# sparkfun-photon-redboard.net
KiCad netlist of a schematic drawn in EAGLE
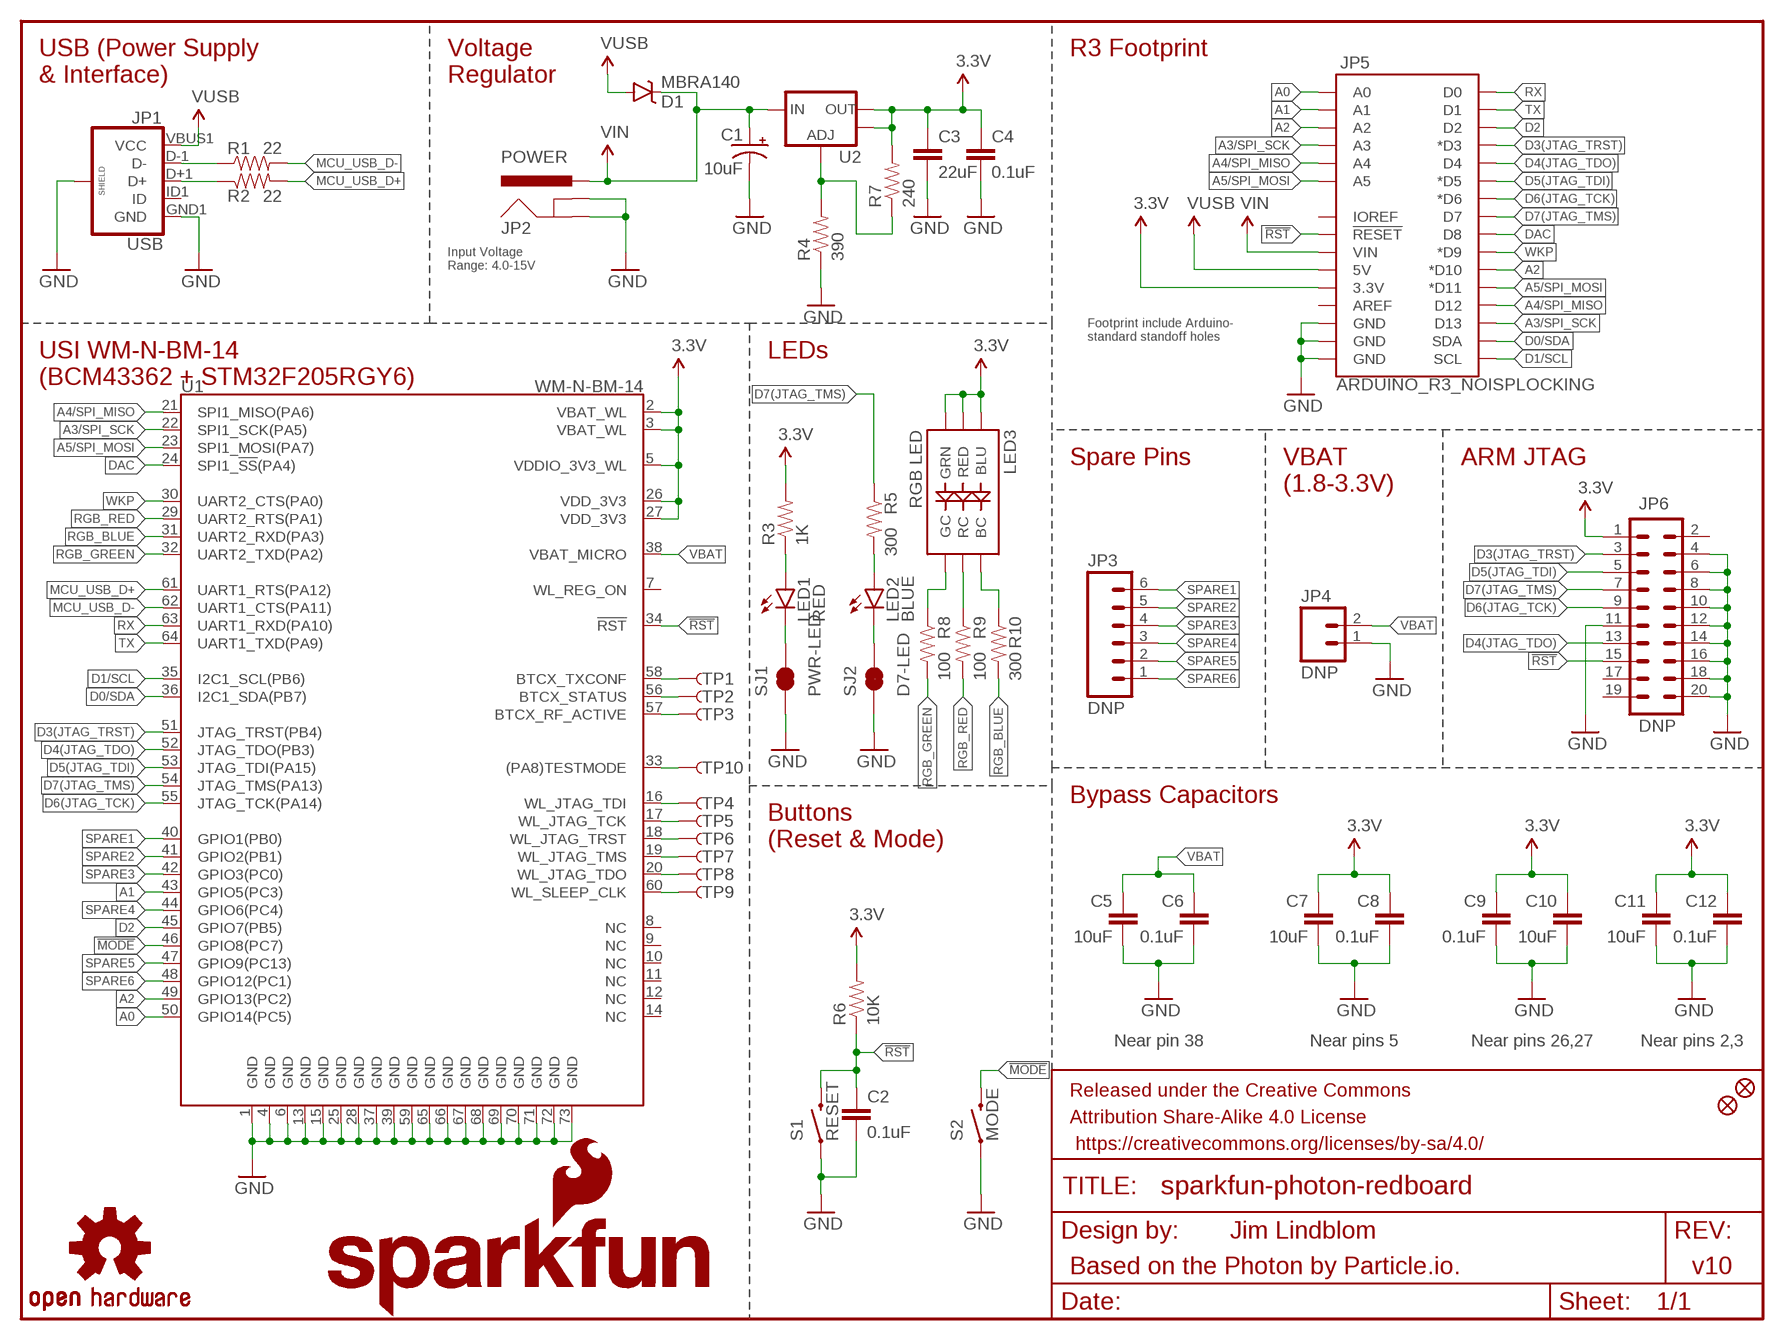
[diagram p0: schematic, sheet 1]

(export (version "E")
  (design (tool "Eeschema 10.0.6"))
  (components
    (comp (ref "C1")
      (value "10uF")
      (footprint "eagle-import:EIA3216")
      (libsource (lib "eagle-import") (part "10UF-16V-10%(TANT)"))
    )
    (comp (ref "C2")
      (value "0.1uF")
      (footprint "eagle-import:0603-CAP")
      (libsource (lib "eagle-import") (part "0.1UF-25V(+80/-20%)(0603)"))
    )
    (comp (ref "C3")
      (value "22uF")
      (footprint "eagle-import:0805")
      (libsource (lib "eagle-import") (part "22UF-6.3V-20%(0805)"))
    )
    (comp (ref "C4")
      (value "0.1uF")
      (footprint "eagle-import:0603-CAP")
      (libsource (lib "eagle-import") (part "0.1UF-25V(+80/-20%)(0603)"))
    )
    (comp (ref "C5")
      (value "10uF")
      (footprint "eagle-import:0603-CAP")
      (libsource (lib "eagle-import") (part "10UF-6.3V-20%(0603)"))
    )
    (comp (ref "C6")
      (value "0.1uF")
      (footprint "eagle-import:0603-CAP")
      (libsource (lib "eagle-import") (part "0.1UF-25V(+80/-20%)(0603)"))
    )
    (comp (ref "C7")
      (value "10uF")
      (footprint "eagle-import:0603-CAP")
      (libsource (lib "eagle-import") (part "10UF-6.3V-20%(0603)"))
    )
    (comp (ref "C8")
      (value "0.1uF")
      (footprint "eagle-import:0603-CAP")
      (libsource (lib "eagle-import") (part "0.1UF-25V(+80/-20%)(0603)"))
    )
    (comp (ref "C9")
      (value "0.1uF")
      (footprint "eagle-import:0603-CAP")
      (libsource (lib "eagle-import") (part "0.1UF-25V(+80/-20%)(0603)"))
    )
    (comp (ref "C10")
      (value "10uF")
      (footprint "eagle-import:0603-CAP")
      (libsource (lib "eagle-import") (part "10UF-6.3V-20%(0603)"))
    )
    (comp (ref "C11")
      (value "10uF")
      (footprint "eagle-import:0603-CAP")
      (libsource (lib "eagle-import") (part "10UF-6.3V-20%(0603)"))
    )
    (comp (ref "C12")
      (value "0.1uF")
      (footprint "eagle-import:0603-CAP")
      (libsource (lib "eagle-import") (part "0.1UF-25V(+80/-20%)(0603)"))
    )
    (comp (ref "D1")
      (value "MBRA140")
      (footprint "eagle-import:SMA-DIODE")
      (libsource (lib "eagle-import") (part "DIODE-SCHOTTKY-MBRA140"))
    )
    (comp (ref "FID1")
      (value "FIDUCIAL1X2")
      (footprint "eagle-import:FIDUCIAL-1X2")
      (libsource (lib "eagle-import") (part "FIDUCIAL1X2"))
    )
    (comp (ref "FID2")
      (value "FIDUCIAL1X2")
      (footprint "eagle-import:FIDUCIAL-1X2")
      (libsource (lib "eagle-import") (part "FIDUCIAL1X2"))
    )
    (comp (ref "FRAME1")
      (value "FRAME-LETTER")
      (footprint "eagle-import:CREATIVE_COMMONS")
      (fields (field (name "DESIGNER") "Jim Lindblom"))
      (libsource (lib "eagle-import") (part "FRAME-LETTER"))
    )
    (comp (ref "JP1")
      (value "USB")
      (footprint "eagle-import:USB-B-MICRO-SMD_V03")
      (libsource (lib "eagle-import") (part "USB_MICROB_PLUGCONN-11752"))
    )
    (comp (ref "JP2")
      (value "POWER")
      (footprint "eagle-import:POWER_JACK_PTH_LOCK")
      (libsource (lib "eagle-import") (part "POWER_JACKPTH_LOCK"))
    )
    (comp (ref "JP3")
      (value "DNP")
      (footprint "eagle-import:1X06")
      (libsource (lib "eagle-import") (part "M06SILK_FEMALE_PTH"))
    )
    (comp (ref "JP4")
      (value "DNP")
      (footprint "eagle-import:1X02")
      (libsource (lib "eagle-import") (part "M02PTH"))
    )
    (comp (ref "JP5")
      (value "ARDUINO_R3_NOISPLOCKING")
      (footprint "eagle-import:ARDUINO_R3_NOISP_LOCKING")
      (libsource (lib "eagle-import") (part "ARDUINO_R3_NOISPLOCKING"))
    )
    (comp (ref "JP6")
      (value "DNP")
      (footprint "eagle-import:2X10")
      (libsource (lib "eagle-import") (part "M10X2"))
    )
    (comp (ref "LED1")
      (value "RED")
      (footprint "eagle-import:LED-1206")
      (libsource (lib "eagle-import") (part "LED-RED1206"))
    )
    (comp (ref "LED2")
      (value "BLUE")
      (footprint "eagle-import:LED-1206")
      (libsource (lib "eagle-import") (part "LED-BLUE1206"))
    )
    (comp (ref "LED3")
      (value "RGB LED")
      (footprint "eagle-import:PLCC-6-LED")
      (libsource (lib "eagle-import") (part "LED-TRICOLOR-NO-COMPLCC-6-SMD"))
    )
    (comp (ref "LOGO1")
      (value "OSHW-LOGOM")
      (footprint "eagle-import:OSHW-LOGO-M")
      (libsource (lib "eagle-import") (part "OSHW-LOGOM"))
    )
    (comp (ref "LOGO2")
      (value "SFE_LOGO_NAME_FLAME.2_INCH")
      (footprint "eagle-import:SFE_LOGO_NAME_FLAME_.2")
      (libsource (lib "eagle-import") (part "SFE_LOGO_NAME_FLAME.2_INCH"))
    )
    (comp (ref "LOGO3")
      (value "SFE_LOGO_NAME_FLAME.4_INCH")
      (footprint "eagle-import:SFE_LOGO_NAME_FLAME_.4")
      (libsource (lib "eagle-import") (part "SFE_LOGO_NAME_FLAME.4_INCH"))
    )
    (comp (ref "R1")
      (value "22")
      (footprint "eagle-import:0603-RES")
      (libsource (lib "eagle-import") (part "22OHM1/10W1%(0603)"))
    )
    (comp (ref "R2")
      (value "22")
      (footprint "eagle-import:0603-RES")
      (libsource (lib "eagle-import") (part "22OHM1/10W1%(0603)"))
    )
    (comp (ref "R3")
      (value "1K")
      (footprint "eagle-import:0603-RES")
      (libsource (lib "eagle-import") (part "1KOHM-1/10W-1%(0603)"))
    )
    (comp (ref "R4")
      (value "390")
      (footprint "eagle-import:0603-RES")
      (libsource (lib "eagle-import") (part "390OHM1/10W1%(0603)"))
    )
    (comp (ref "R5")
      (value "300")
      (footprint "eagle-import:0603-RES")
      (libsource (lib "eagle-import") (part "300OHM-1/10W-1%(0603)"))
    )
    (comp (ref "R6")
      (value "10K")
      (footprint "eagle-import:0603-RES")
      (libsource (lib "eagle-import") (part "10KOHM-1/10W-1%(0603)0603"))
    )
    (comp (ref "R7")
      (value "240")
      (footprint "eagle-import:0603-RES")
      (libsource (lib "eagle-import") (part "240OHM1/10W1%(0603)"))
    )
    (comp (ref "R8")
      (value "100")
      (footprint "eagle-import:0603-RES")
      (libsource (lib "eagle-import") (part "100OHM-1/10W-1%(0603)"))
    )
    (comp (ref "R9")
      (value "100")
      (footprint "eagle-import:0603-RES")
      (libsource (lib "eagle-import") (part "100OHM-1/10W-1%(0603)"))
    )
    (comp (ref "R10")
      (value "300")
      (footprint "eagle-import:0603-RES")
      (libsource (lib "eagle-import") (part "300OHM-1/10W-1%(0603)"))
    )
    (comp (ref "S1")
      (value "RESET")
      (footprint "eagle-import:TACTILE-PTH")
      (libsource (lib "eagle-import") (part "SWITCH-MOMENTARY-2PTH"))
    )
    (comp (ref "S2")
      (value "MODE")
      (footprint "eagle-import:TACTILE-PTH")
      (libsource (lib "eagle-import") (part "SWITCH-MOMENTARY-2PTH"))
    )
    (comp (ref "SJ1")
      (value "PWR-LED")
      (footprint "eagle-import:PAD-JUMPER-2-NC_BY_TRACE_YES_SILK")
      (libsource (lib "eagle-import") (part "JUMPER-PAD-2-NC_BY_TRACE"))
    )
    (comp (ref "SJ2")
      (value "D7-LED")
      (footprint "eagle-import:PAD-JUMPER-2-NC_BY_TRACE_YES_SILK")
      (libsource (lib "eagle-import") (part "JUMPER-PAD-2-NC_BY_TRACE"))
    )
    (comp (ref "TP1")
      (value "TEST-POINTTP_15TH_THRU")
      (footprint "eagle-import:TP_15TH")
      (libsource (lib "eagle-import") (part "TEST-POINTTP_15TH_THRU"))
    )
    (comp (ref "TP2")
      (value "TEST-POINTTP_15TH_THRU")
      (footprint "eagle-import:TP_15TH")
      (libsource (lib "eagle-import") (part "TEST-POINTTP_15TH_THRU"))
    )
    (comp (ref "TP3")
      (value "TEST-POINTTP_15TH_THRU")
      (footprint "eagle-import:TP_15TH")
      (libsource (lib "eagle-import") (part "TEST-POINTTP_15TH_THRU"))
    )
    (comp (ref "TP4")
      (value "TEST-POINTTP_15TH_THRU")
      (footprint "eagle-import:TP_15TH")
      (libsource (lib "eagle-import") (part "TEST-POINTTP_15TH_THRU"))
    )
    (comp (ref "TP5")
      (value "TEST-POINTTP_15TH_THRU")
      (footprint "eagle-import:TP_15TH")
      (libsource (lib "eagle-import") (part "TEST-POINTTP_15TH_THRU"))
    )
    (comp (ref "TP6")
      (value "TEST-POINTTP_15TH_THRU")
      (footprint "eagle-import:TP_15TH")
      (libsource (lib "eagle-import") (part "TEST-POINTTP_15TH_THRU"))
    )
    (comp (ref "TP7")
      (value "TEST-POINTTP_15TH_THRU")
      (footprint "eagle-import:TP_15TH")
      (libsource (lib "eagle-import") (part "TEST-POINTTP_15TH_THRU"))
    )
    (comp (ref "TP8")
      (value "TEST-POINTTP_15TH_THRU")
      (footprint "eagle-import:TP_15TH")
      (libsource (lib "eagle-import") (part "TEST-POINTTP_15TH_THRU"))
    )
    (comp (ref "TP9")
      (value "TEST-POINTTP_15TH_THRU")
      (footprint "eagle-import:TP_15TH")
      (libsource (lib "eagle-import") (part "TEST-POINTTP_15TH_THRU"))
    )
    (comp (ref "TP10")
      (value "TEST-POINTTP_15TH_THRU")
      (footprint "eagle-import:TP_15TH")
      (libsource (lib "eagle-import") (part "TEST-POINTTP_15TH_THRU"))
    )
    (comp (ref "U1")
      (value "WM-N-BM-14")
      (footprint "eagle-import:WM-N-BM-14")
      (libsource (lib "eagle-import") (part "WM-N-BM-14"))
    )
    (comp (ref "U2")
      (value "V_REG_LM1117SOT223")
      (footprint "eagle-import:SOT223")
      (libsource (lib "eagle-import") (part "V_REG_LM1117SOT223"))
    )
  )
  (nets
    (net (code "1") (name "/~{MODE}") (class "Default")
      (node (ref "S2") (pin "3") (pinfunction "2_3") (pintype "passive"))
      (node (ref "U1") (pin "46") (pinfunction "GPIO8(PC7)_46") (pintype "bidirectional"))
    )
    (net (code "2") (name "/~{RST}") (class "Default")
      (node (ref "C2") (pin "1") (pinfunction "1_1") (pintype "passive"))
      (node (ref "JP5") (pin "RESET@1") (pinfunction "~{RESET}_RESET@1") (pintype "bidirectional"))
      (node (ref "JP6") (pin "15") (pinfunction "15_15") (pintype "passive"))
      (node (ref "R6") (pin "1") (pinfunction "1_1") (pintype "passive"))
      (node (ref "S1") (pin "3") (pinfunction "2_3") (pintype "passive"))
      (node (ref "U1") (pin "34") (pinfunction "~{RST}_34") (pintype "bidirectional"))
    )
    (net (code "3") (name "3.3V") (class "Default")
      (node (ref "C10") (pin "1") (pinfunction "1_1") (pintype "passive"))
      (node (ref "C11") (pin "1") (pinfunction "1_1") (pintype "passive"))
      (node (ref "C12") (pin "1") (pinfunction "1_1") (pintype "passive"))
      (node (ref "C3") (pin "1") (pinfunction "1_1") (pintype "passive"))
      (node (ref "C4") (pin "1") (pinfunction "1_1") (pintype "passive"))
      (node (ref "C7") (pin "1") (pinfunction "1_1") (pintype "passive"))
      (node (ref "C8") (pin "1") (pinfunction "1_1") (pintype "passive"))
      (node (ref "C9") (pin "1") (pinfunction "1_1") (pintype "passive"))
      (node (ref "JP5") (pin "3.3V") (pinfunction "3.3V_3.3V") (pintype "bidirectional"))
      (node (ref "JP6") (pin "1") (pinfunction "1_1") (pintype "passive"))
      (node (ref "LED3") (pin "AB") (pinfunction "BLU_AB") (pintype "bidirectional"))
      (node (ref "LED3") (pin "AG") (pinfunction "GRN_AG") (pintype "bidirectional"))
      (node (ref "LED3") (pin "AR") (pinfunction "RED_AR") (pintype "bidirectional"))
      (node (ref "R3") (pin "2") (pinfunction "2_2") (pintype "passive"))
      (node (ref "R6") (pin "2") (pinfunction "2_2") (pintype "passive"))
      (node (ref "R7") (pin "2") (pinfunction "2_2") (pintype "passive"))
      (node (ref "U1") (pin "2") (pinfunction "VBAT_WL_2") (pintype "bidirectional"))
      (node (ref "U1") (pin "26") (pinfunction "VDD_3V3_26") (pintype "bidirectional"))
      (node (ref "U1") (pin "27") (pinfunction "VDD_3V3_27") (pintype "bidirectional"))
      (node (ref "U1") (pin "3") (pinfunction "VBAT_WL_3") (pintype "bidirectional"))
      (node (ref "U1") (pin "5") (pinfunction "VDDIO_3V3_WL_5") (pintype "bidirectional"))
      (node (ref "U2") (pin "2") (pinfunction "OUT_2") (pintype "output"))
      (node (ref "U2") (pin "4") (pinfunction "OUT_4") (pintype "output"))
    )
    (net (code "4") (name "A0") (class "Default")
      (node (ref "JP5") (pin "A0") (pinfunction "A0_A0") (pintype "bidirectional"))
      (node (ref "U1") (pin "50") (pinfunction "GPIO14(PC5)_50") (pintype "bidirectional"))
    )
    (net (code "5") (name "A1") (class "Default")
      (node (ref "JP5") (pin "A1") (pinfunction "A1_A1") (pintype "bidirectional"))
      (node (ref "U1") (pin "43") (pinfunction "GPIO5(PC3)_43") (pintype "bidirectional"))
    )
    (net (code "6") (name "A2") (class "Default")
      (node (ref "JP5") (pin "A2") (pinfunction "A2_A2") (pintype "bidirectional"))
      (node (ref "JP5") (pin "D10") (pinfunction "*D10_D10") (pintype "bidirectional"))
      (node (ref "U1") (pin "49") (pinfunction "GPIO13(PC2)_49") (pintype "bidirectional"))
    )
    (net (code "7") (name "A3{slash}SPI_SCK") (class "Default")
      (node (ref "JP5") (pin "A3") (pinfunction "A3_A3") (pintype "bidirectional"))
      (node (ref "JP5") (pin "D13") (pinfunction "D13_D13") (pintype "bidirectional"))
      (node (ref "U1") (pin "22") (pinfunction "SPI1_SCK(PA5)_22") (pintype "bidirectional"))
    )
    (net (code "8") (name "A4{slash}SPI_MISO") (class "Default")
      (node (ref "JP5") (pin "A4") (pinfunction "A4_A4") (pintype "bidirectional"))
      (node (ref "JP5") (pin "D12") (pinfunction "D12_D12") (pintype "bidirectional"))
      (node (ref "U1") (pin "21") (pinfunction "SPI1_MISO(PA6)_21") (pintype "bidirectional"))
    )
    (net (code "9") (name "A5{slash}SPI_MOSI") (class "Default")
      (node (ref "JP5") (pin "A5") (pinfunction "A5_A5") (pintype "bidirectional"))
      (node (ref "JP5") (pin "D11") (pinfunction "*D11_D11") (pintype "bidirectional"))
      (node (ref "U1") (pin "23") (pinfunction "SPI1_MOSI(PA7)_23") (pintype "bidirectional"))
    )
    (net (code "10") (name "D0{slash}SDA") (class "Default")
      (node (ref "JP5") (pin "SDA") (pinfunction "SDA_SDA") (pintype "bidirectional"))
      (node (ref "U1") (pin "36") (pinfunction "I2C1_SDA(PB7)_36") (pintype "bidirectional"))
    )
    (net (code "11") (name "D1{slash}SCL") (class "Default")
      (node (ref "JP5") (pin "SCL") (pinfunction "SCL_SCL") (pintype "bidirectional"))
      (node (ref "U1") (pin "35") (pinfunction "I2C1_SCL(PB6)_35") (pintype "bidirectional"))
    )
    (net (code "12") (name "D2") (class "Default")
      (node (ref "JP5") (pin "D2") (pinfunction "D2_D2") (pintype "bidirectional"))
      (node (ref "U1") (pin "45") (pinfunction "GPIO7(PB5)_45") (pintype "bidirectional"))
    )
    (net (code "13") (name "D3(JTAG_TRST)") (class "Default")
      (node (ref "JP5") (pin "D3") (pinfunction "*D3_D3") (pintype "bidirectional"))
      (node (ref "JP6") (pin "3") (pinfunction "3_3") (pintype "passive"))
      (node (ref "U1") (pin "51") (pinfunction "JTAG_TRST(PB4)_51") (pintype "bidirectional"))
    )
    (net (code "14") (name "D4(JTAG_TDO)") (class "Default")
      (node (ref "JP5") (pin "D4") (pinfunction "D4_D4") (pintype "bidirectional"))
      (node (ref "JP6") (pin "13") (pinfunction "13_13") (pintype "passive"))
      (node (ref "U1") (pin "52") (pinfunction "JTAG_TDO(PB3)_52") (pintype "bidirectional"))
    )
    (net (code "15") (name "D5(JTAG_TDI)") (class "Default")
      (node (ref "JP5") (pin "D5") (pinfunction "*D5_D5") (pintype "bidirectional"))
      (node (ref "JP6") (pin "5") (pinfunction "5_5") (pintype "passive"))
      (node (ref "U1") (pin "53") (pinfunction "JTAG_TDI(PA15)_53") (pintype "bidirectional"))
    )
    (net (code "16") (name "D6(JTAG_TCK)") (class "Default")
      (node (ref "JP5") (pin "D6") (pinfunction "*D6_D6") (pintype "bidirectional"))
      (node (ref "JP6") (pin "9") (pinfunction "9_9") (pintype "passive"))
      (node (ref "U1") (pin "55") (pinfunction "JTAG_TCK(PA14)_55") (pintype "bidirectional"))
    )
    (net (code "17") (name "D7(JTAG_TMS)") (class "Default")
      (node (ref "JP5") (pin "D7") (pinfunction "D7_D7") (pintype "bidirectional"))
      (node (ref "JP6") (pin "7") (pinfunction "7_7") (pintype "passive"))
      (node (ref "R5") (pin "1") (pinfunction "1_1") (pintype "passive"))
      (node (ref "U1") (pin "54") (pinfunction "JTAG_TMS(PA13)_54") (pintype "bidirectional"))
    )
    (net (code "18") (name "DAC") (class "Default")
      (node (ref "JP5") (pin "D8") (pinfunction "D8_D8") (pintype "bidirectional"))
      (node (ref "U1") (pin "24") (pinfunction "SPI1_~{SS}(PA4)_24") (pintype "bidirectional"))
    )
    (net (code "19") (name "GND") (class "Default")
      (node (ref "C1") (pin "C") (pinfunction "-_C") (pintype "passive"))
      (node (ref "C10") (pin "2") (pinfunction "2_2") (pintype "passive"))
      (node (ref "C11") (pin "2") (pinfunction "2_2") (pintype "passive"))
      (node (ref "C12") (pin "2") (pinfunction "2_2") (pintype "passive"))
      (node (ref "C2") (pin "2") (pinfunction "2_2") (pintype "passive"))
      (node (ref "C3") (pin "2") (pinfunction "2_2") (pintype "passive"))
      (node (ref "C4") (pin "2") (pinfunction "2_2") (pintype "passive"))
      (node (ref "C5") (pin "2") (pinfunction "2_2") (pintype "passive"))
      (node (ref "C6") (pin "2") (pinfunction "2_2") (pintype "passive"))
      (node (ref "C7") (pin "2") (pinfunction "2_2") (pintype "passive"))
      (node (ref "C8") (pin "2") (pinfunction "2_2") (pintype "passive"))
      (node (ref "C9") (pin "2") (pinfunction "2_2") (pintype "passive"))
      (node (ref "JP1") (pin "GND1") (pinfunction "GND_GND1") (pintype "bidirectional"))
      (node (ref "JP1") (pin "SHIELD1") (pinfunction "SHIELD_SHIELD1") (pintype "bidirectional"))
      (node (ref "JP1") (pin "SHIELD2") (pinfunction "SHIELD_SHIELD2") (pintype "bidirectional"))
      (node (ref "JP1") (pin "SHIELD3") (pinfunction "SHIELD_SHIELD3") (pintype "bidirectional"))
      (node (ref "JP2") (pin "GND") (pinfunction "GND_GND") (pintype "bidirectional"))
      (node (ref "JP2") (pin "GNDBREAK") (pinfunction "GNDBREAK_GNDBREAK") (pintype "bidirectional"))
      (node (ref "JP4") (pin "1") (pinfunction "1_1") (pintype "passive"))
      (node (ref "JP5") (pin "GND@1") (pinfunction "GND_GND@1") (pintype "bidirectional"))
      (node (ref "JP5") (pin "GND@2") (pinfunction "GND_GND@2") (pintype "bidirectional"))
      (node (ref "JP5") (pin "GND@3") (pinfunction "GND_GND@3") (pintype "bidirectional"))
      (node (ref "JP6") (pin "10") (pinfunction "10_10") (pintype "passive"))
      (node (ref "JP6") (pin "11") (pinfunction "11_11") (pintype "passive"))
      (node (ref "JP6") (pin "12") (pinfunction "12_12") (pintype "passive"))
      (node (ref "JP6") (pin "14") (pinfunction "14_14") (pintype "passive"))
      (node (ref "JP6") (pin "16") (pinfunction "16_16") (pintype "passive"))
      (node (ref "JP6") (pin "18") (pinfunction "18_18") (pintype "passive"))
      (node (ref "JP6") (pin "20") (pinfunction "20_20") (pintype "passive"))
      (node (ref "JP6") (pin "4") (pinfunction "4_4") (pintype "passive"))
      (node (ref "JP6") (pin "6") (pinfunction "6_6") (pintype "passive"))
      (node (ref "JP6") (pin "8") (pinfunction "8_8") (pintype "passive"))
      (node (ref "R4") (pin "1") (pinfunction "1_1") (pintype "passive"))
      (node (ref "S1") (pin "1") (pinfunction "1_1") (pintype "passive"))
      (node (ref "S2") (pin "1") (pinfunction "1_1") (pintype "passive"))
      (node (ref "SJ1") (pin "1") (pinfunction "1_1") (pintype "passive"))
      (node (ref "SJ2") (pin "1") (pinfunction "1_1") (pintype "passive"))
      (node (ref "U1") (pin "1") (pinfunction "GND_1") (pintype "bidirectional"))
      (node (ref "U1") (pin "13") (pinfunction "GND_13") (pintype "bidirectional"))
      (node (ref "U1") (pin "15") (pinfunction "GND_15") (pintype "bidirectional"))
      (node (ref "U1") (pin "25") (pinfunction "GND_25") (pintype "bidirectional"))
      (node (ref "U1") (pin "28") (pinfunction "GND_28") (pintype "bidirectional"))
      (node (ref "U1") (pin "37") (pinfunction "GND_37") (pintype "bidirectional"))
      (node (ref "U1") (pin "39") (pinfunction "GND_39") (pintype "bidirectional"))
      (node (ref "U1") (pin "4") (pinfunction "GND_4") (pintype "bidirectional"))
      (node (ref "U1") (pin "59") (pinfunction "GND_59") (pintype "bidirectional"))
      (node (ref "U1") (pin "6") (pinfunction "GND_6") (pintype "bidirectional"))
      (node (ref "U1") (pin "65") (pinfunction "GND_65") (pintype "bidirectional"))
      (node (ref "U1") (pin "66") (pinfunction "GND_66") (pintype "bidirectional"))
      (node (ref "U1") (pin "67") (pinfunction "GND_67") (pintype "bidirectional"))
      (node (ref "U1") (pin "68") (pinfunction "GND_68") (pintype "bidirectional"))
      (node (ref "U1") (pin "69") (pinfunction "GND_69") (pintype "bidirectional"))
      (node (ref "U1") (pin "70") (pinfunction "GND_70") (pintype "bidirectional"))
      (node (ref "U1") (pin "71") (pinfunction "GND_71") (pintype "bidirectional"))
      (node (ref "U1") (pin "72") (pinfunction "GND_72") (pintype "bidirectional"))
      (node (ref "U1") (pin "73") (pinfunction "GND_73") (pintype "bidirectional"))
    )
    (net (code "20") (name "MCU_USB_D+") (class "Default")
      (node (ref "R2") (pin "2") (pinfunction "2_2") (pintype "passive"))
      (node (ref "U1") (pin "61") (pinfunction "UART1_RTS(PA12)_61") (pintype "bidirectional"))
    )
    (net (code "21") (name "MCU_USB_D-") (class "Default")
      (node (ref "R1") (pin "2") (pinfunction "2_2") (pintype "passive"))
      (node (ref "U1") (pin "62") (pinfunction "UART1_CTS(PA11)_62") (pintype "bidirectional"))
    )
    (net (code "22") (name "Net-(JP1-D+)") (class "Default")
      (node (ref "JP1") (pin "D+1") (pinfunction "D+_D+1") (pintype "bidirectional"))
      (node (ref "R2") (pin "1") (pinfunction "1_1") (pintype "passive"))
    )
    (net (code "23") (name "Net-(JP1-D-)") (class "Default")
      (node (ref "JP1") (pin "D-1") (pinfunction "D-_D-1") (pintype "bidirectional"))
      (node (ref "R1") (pin "1") (pinfunction "1_1") (pintype "passive"))
    )
    (net (code "24") (name "Net-(LED1-PadA)") (class "Default")
      (node (ref "LED1") (pin "A") (pinfunction "A_A") (pintype "passive"))
      (node (ref "R3") (pin "1") (pinfunction "1_1") (pintype "passive"))
    )
    (net (code "25") (name "Net-(LED1-PadC)") (class "Default")
      (node (ref "LED1") (pin "C") (pinfunction "C_C") (pintype "passive"))
      (node (ref "SJ1") (pin "2") (pinfunction "2_2") (pintype "passive"))
    )
    (net (code "26") (name "Net-(LED2-PadA)") (class "Default")
      (node (ref "LED2") (pin "A") (pinfunction "A_A") (pintype "passive"))
      (node (ref "R5") (pin "2") (pinfunction "2_2") (pintype "passive"))
    )
    (net (code "27") (name "Net-(LED2-PadC)") (class "Default")
      (node (ref "LED2") (pin "C") (pinfunction "C_C") (pintype "passive"))
      (node (ref "SJ2") (pin "2") (pinfunction "2_2") (pintype "passive"))
    )
    (net (code "28") (name "Net-(LED3-BC)") (class "Default")
      (node (ref "LED3") (pin "CB") (pinfunction "BC_CB") (pintype "bidirectional"))
      (node (ref "R10") (pin "1") (pinfunction "1_1") (pintype "passive"))
    )
    (net (code "29") (name "Net-(LED3-GC)") (class "Default")
      (node (ref "LED3") (pin "CG") (pinfunction "GC_CG") (pintype "bidirectional"))
      (node (ref "R8") (pin "1") (pinfunction "1_1") (pintype "passive"))
    )
    (net (code "30") (name "Net-(LED3-RC)") (class "Default")
      (node (ref "LED3") (pin "CR") (pinfunction "RC_CR") (pintype "bidirectional"))
      (node (ref "R9") (pin "1") (pinfunction "1_1") (pintype "passive"))
    )
    (net (code "31") (name "Net-(TP1-1)") (class "Default")
      (node (ref "TP1") (pin "P$1") (pinfunction "1_P$1") (pintype "bidirectional"))
      (node (ref "U1") (pin "58") (pinfunction "BTCX_TXCONF_58") (pintype "bidirectional"))
    )
    (net (code "32") (name "Net-(TP2-1)") (class "Default")
      (node (ref "TP2") (pin "P$1") (pinfunction "1_P$1") (pintype "bidirectional"))
      (node (ref "U1") (pin "56") (pinfunction "BTCX_STATUS_56") (pintype "bidirectional"))
    )
    (net (code "33") (name "Net-(TP3-1)") (class "Default")
      (node (ref "TP3") (pin "P$1") (pinfunction "1_P$1") (pintype "bidirectional"))
      (node (ref "U1") (pin "57") (pinfunction "BTCX_RF_ACTIVE_57") (pintype "bidirectional"))
    )
    (net (code "34") (name "Net-(TP4-1)") (class "Default")
      (node (ref "TP4") (pin "P$1") (pinfunction "1_P$1") (pintype "bidirectional"))
      (node (ref "U1") (pin "16") (pinfunction "WL_JTAG_TDI_16") (pintype "bidirectional"))
    )
    (net (code "35") (name "Net-(TP5-1)") (class "Default")
      (node (ref "TP5") (pin "P$1") (pinfunction "1_P$1") (pintype "bidirectional"))
      (node (ref "U1") (pin "17") (pinfunction "WL_JTAG_TCK_17") (pintype "bidirectional"))
    )
    (net (code "36") (name "Net-(TP6-1)") (class "Default")
      (node (ref "TP6") (pin "P$1") (pinfunction "1_P$1") (pintype "bidirectional"))
      (node (ref "U1") (pin "18") (pinfunction "WL_JTAG_TRST_18") (pintype "bidirectional"))
    )
    (net (code "37") (name "Net-(TP7-1)") (class "Default")
      (node (ref "TP7") (pin "P$1") (pinfunction "1_P$1") (pintype "bidirectional"))
      (node (ref "U1") (pin "19") (pinfunction "WL_JTAG_TMS_19") (pintype "bidirectional"))
    )
    (net (code "38") (name "Net-(TP8-1)") (class "Default")
      (node (ref "TP8") (pin "P$1") (pinfunction "1_P$1") (pintype "bidirectional"))
      (node (ref "U1") (pin "20") (pinfunction "WL_JTAG_TDO_20") (pintype "bidirectional"))
    )
    (net (code "39") (name "Net-(TP9-1)") (class "Default")
      (node (ref "TP9") (pin "P$1") (pinfunction "1_P$1") (pintype "bidirectional"))
      (node (ref "U1") (pin "60") (pinfunction "WL_SLEEP_CLK_60") (pintype "bidirectional"))
    )
    (net (code "40") (name "Net-(TP10-1)") (class "Default")
      (node (ref "TP10") (pin "P$1") (pinfunction "1_P$1") (pintype "bidirectional"))
      (node (ref "U1") (pin "33") (pinfunction "(PA8)TESTMODE_33") (pintype "bidirectional"))
    )
    (net (code "41") (name "Net-(U2-ADJ)") (class "Default")
      (node (ref "R4") (pin "2") (pinfunction "2_2") (pintype "passive"))
      (node (ref "R7") (pin "1") (pinfunction "1_1") (pintype "passive"))
      (node (ref "U2") (pin "1") (pinfunction "ADJ_1") (pintype "input"))
    )
    (net (code "42") (name "RGB_BLUE") (class "Default")
      (node (ref "R10") (pin "2") (pinfunction "2_2") (pintype "passive"))
      (node (ref "U1") (pin "31") (pinfunction "UART2_RXD(PA3)_31") (pintype "bidirectional"))
    )
    (net (code "43") (name "RGB_GREEN") (class "Default")
      (node (ref "R8") (pin "2") (pinfunction "2_2") (pintype "passive"))
      (node (ref "U1") (pin "32") (pinfunction "UART2_TXD(PA2)_32") (pintype "bidirectional"))
    )
    (net (code "44") (name "RGB_RED") (class "Default")
      (node (ref "R9") (pin "2") (pinfunction "2_2") (pintype "passive"))
      (node (ref "U1") (pin "29") (pinfunction "UART2_RTS(PA1)_29") (pintype "bidirectional"))
    )
    (net (code "45") (name "RX") (class "Default")
      (node (ref "JP5") (pin "D0") (pinfunction "D0_D0") (pintype "bidirectional"))
      (node (ref "U1") (pin "63") (pinfunction "UART1_RXD(PA10)_63") (pintype "bidirectional"))
    )
    (net (code "46") (name "SPARE1") (class "Default")
      (node (ref "JP3") (pin "6") (pinfunction "6_6") (pintype "passive"))
      (node (ref "U1") (pin "40") (pinfunction "GPIO1(PB0)_40") (pintype "bidirectional"))
    )
    (net (code "47") (name "SPARE2") (class "Default")
      (node (ref "JP3") (pin "5") (pinfunction "5_5") (pintype "passive"))
      (node (ref "U1") (pin "41") (pinfunction "GPIO2(PB1)_41") (pintype "bidirectional"))
    )
    (net (code "48") (name "SPARE3") (class "Default")
      (node (ref "JP3") (pin "4") (pinfunction "4_4") (pintype "passive"))
      (node (ref "U1") (pin "42") (pinfunction "GPIO3(PC0)_42") (pintype "bidirectional"))
    )
    (net (code "49") (name "SPARE4") (class "Default")
      (node (ref "JP3") (pin "3") (pinfunction "3_3") (pintype "passive"))
      (node (ref "U1") (pin "44") (pinfunction "GPIO6(PC4)_44") (pintype "bidirectional"))
    )
    (net (code "50") (name "SPARE5") (class "Default")
      (node (ref "JP3") (pin "2") (pinfunction "2_2") (pintype "passive"))
      (node (ref "U1") (pin "47") (pinfunction "GPIO9(PC13)_47") (pintype "bidirectional"))
    )
    (net (code "51") (name "SPARE6") (class "Default")
      (node (ref "JP3") (pin "1") (pinfunction "1_1") (pintype "passive"))
      (node (ref "U1") (pin "48") (pinfunction "GPIO12(PC1)_48") (pintype "bidirectional"))
    )
    (net (code "52") (name "TX") (class "Default")
      (node (ref "JP5") (pin "D1") (pinfunction "D1_D1") (pintype "bidirectional"))
      (node (ref "U1") (pin "64") (pinfunction "UART1_TXD(PA9)_64") (pintype "bidirectional"))
    )
    (net (code "53") (name "VBAT") (class "Default")
      (node (ref "C5") (pin "1") (pinfunction "1_1") (pintype "passive"))
      (node (ref "C6") (pin "1") (pinfunction "1_1") (pintype "passive"))
      (node (ref "JP4") (pin "2") (pinfunction "2_2") (pintype "passive"))
      (node (ref "U1") (pin "38") (pinfunction "VBAT_MICRO_38") (pintype "bidirectional"))
    )
    (net (code "54") (name "VIN") (class "Default")
      (node (ref "C1") (pin "A") (pinfunction "+_A") (pintype "passive"))
      (node (ref "D1") (pin "C") (pinfunction "C_C") (pintype "passive"))
      (node (ref "JP2") (pin "PWR") (pinfunction "PWR_PWR") (pintype "bidirectional"))
      (node (ref "JP5") (pin "VIN") (pinfunction "VIN_VIN") (pintype "bidirectional"))
      (node (ref "U2") (pin "3") (pinfunction "IN_3") (pintype "input"))
    )
    (net (code "55") (name "VUSB") (class "Default")
      (node (ref "D1") (pin "A") (pinfunction "A_A") (pintype "passive"))
      (node (ref "JP1") (pin "VBUS1") (pinfunction "VCC_VBUS1") (pintype "bidirectional"))
      (node (ref "JP5") (pin "5V") (pinfunction "5V_5V") (pintype "bidirectional"))
    )
    (net (code "56") (name "WKP") (class "Default")
      (node (ref "JP5") (pin "D9") (pinfunction "*D9_D9") (pintype "bidirectional"))
      (node (ref "U1") (pin "30") (pinfunction "UART2_CTS(PA0)_30") (pintype "bidirectional"))
    )
    (net (code "57") (name "unconnected-(JP1-ID-PadID1)") (class "Default")
      (node (ref "JP1") (pin "ID1") (pinfunction "ID_ID1") (pintype "bidirectional"))
    )
    (net (code "58") (name "unconnected-(JP5-PadAREF)") (class "Default")
      (node (ref "JP5") (pin "AREF") (pinfunction "AREF_AREF") (pintype "bidirectional"))
    )
    (net (code "59") (name "unconnected-(JP5-PadIOREF)") (class "Default")
      (node (ref "JP5") (pin "IOREF") (pinfunction "IOREF_IOREF") (pintype "bidirectional"))
    )
    (net (code "60") (name "unconnected-(JP6-Pad2)") (class "Default")
      (node (ref "JP6") (pin "2") (pinfunction "2_2") (pintype "passive"))
    )
    (net (code "61") (name "unconnected-(JP6-Pad17)") (class "Default")
      (node (ref "JP6") (pin "17") (pinfunction "17_17") (pintype "passive"))
    )
    (net (code "62") (name "unconnected-(JP6-Pad19)") (class "Default")
      (node (ref "JP6") (pin "19") (pinfunction "19_19") (pintype "passive"))
    )
    (net (code "63") (name "unconnected-(U1-NC-Pad8)") (class "Default")
      (node (ref "U1") (pin "8") (pinfunction "NC_8") (pintype "bidirectional"))
    )
    (net (code "64") (name "unconnected-(U1-NC-Pad9)") (class "Default")
      (node (ref "U1") (pin "9") (pinfunction "NC_9") (pintype "bidirectional"))
    )
    (net (code "65") (name "unconnected-(U1-NC-Pad10)") (class "Default")
      (node (ref "U1") (pin "10") (pinfunction "NC_10") (pintype "bidirectional"))
    )
    (net (code "66") (name "unconnected-(U1-NC-Pad11)") (class "Default")
      (node (ref "U1") (pin "11") (pinfunction "NC_11") (pintype "bidirectional"))
    )
    (net (code "67") (name "unconnected-(U1-NC-Pad12)") (class "Default")
      (node (ref "U1") (pin "12") (pinfunction "NC_12") (pintype "bidirectional"))
    )
    (net (code "68") (name "unconnected-(U1-NC-Pad14)") (class "Default")
      (node (ref "U1") (pin "14") (pinfunction "NC_14") (pintype "bidirectional"))
    )
    (net (code "69") (name "unconnected-(U1-WL_REG_ON-Pad7)") (class "Default")
      (node (ref "U1") (pin "7") (pinfunction "WL_REG_ON_7") (pintype "bidirectional"))
    )
  )
)
